# Adaptadora_AVR-Mega-U4_44pin.net
KiCad netlist of a schematic drawn in EAGLE
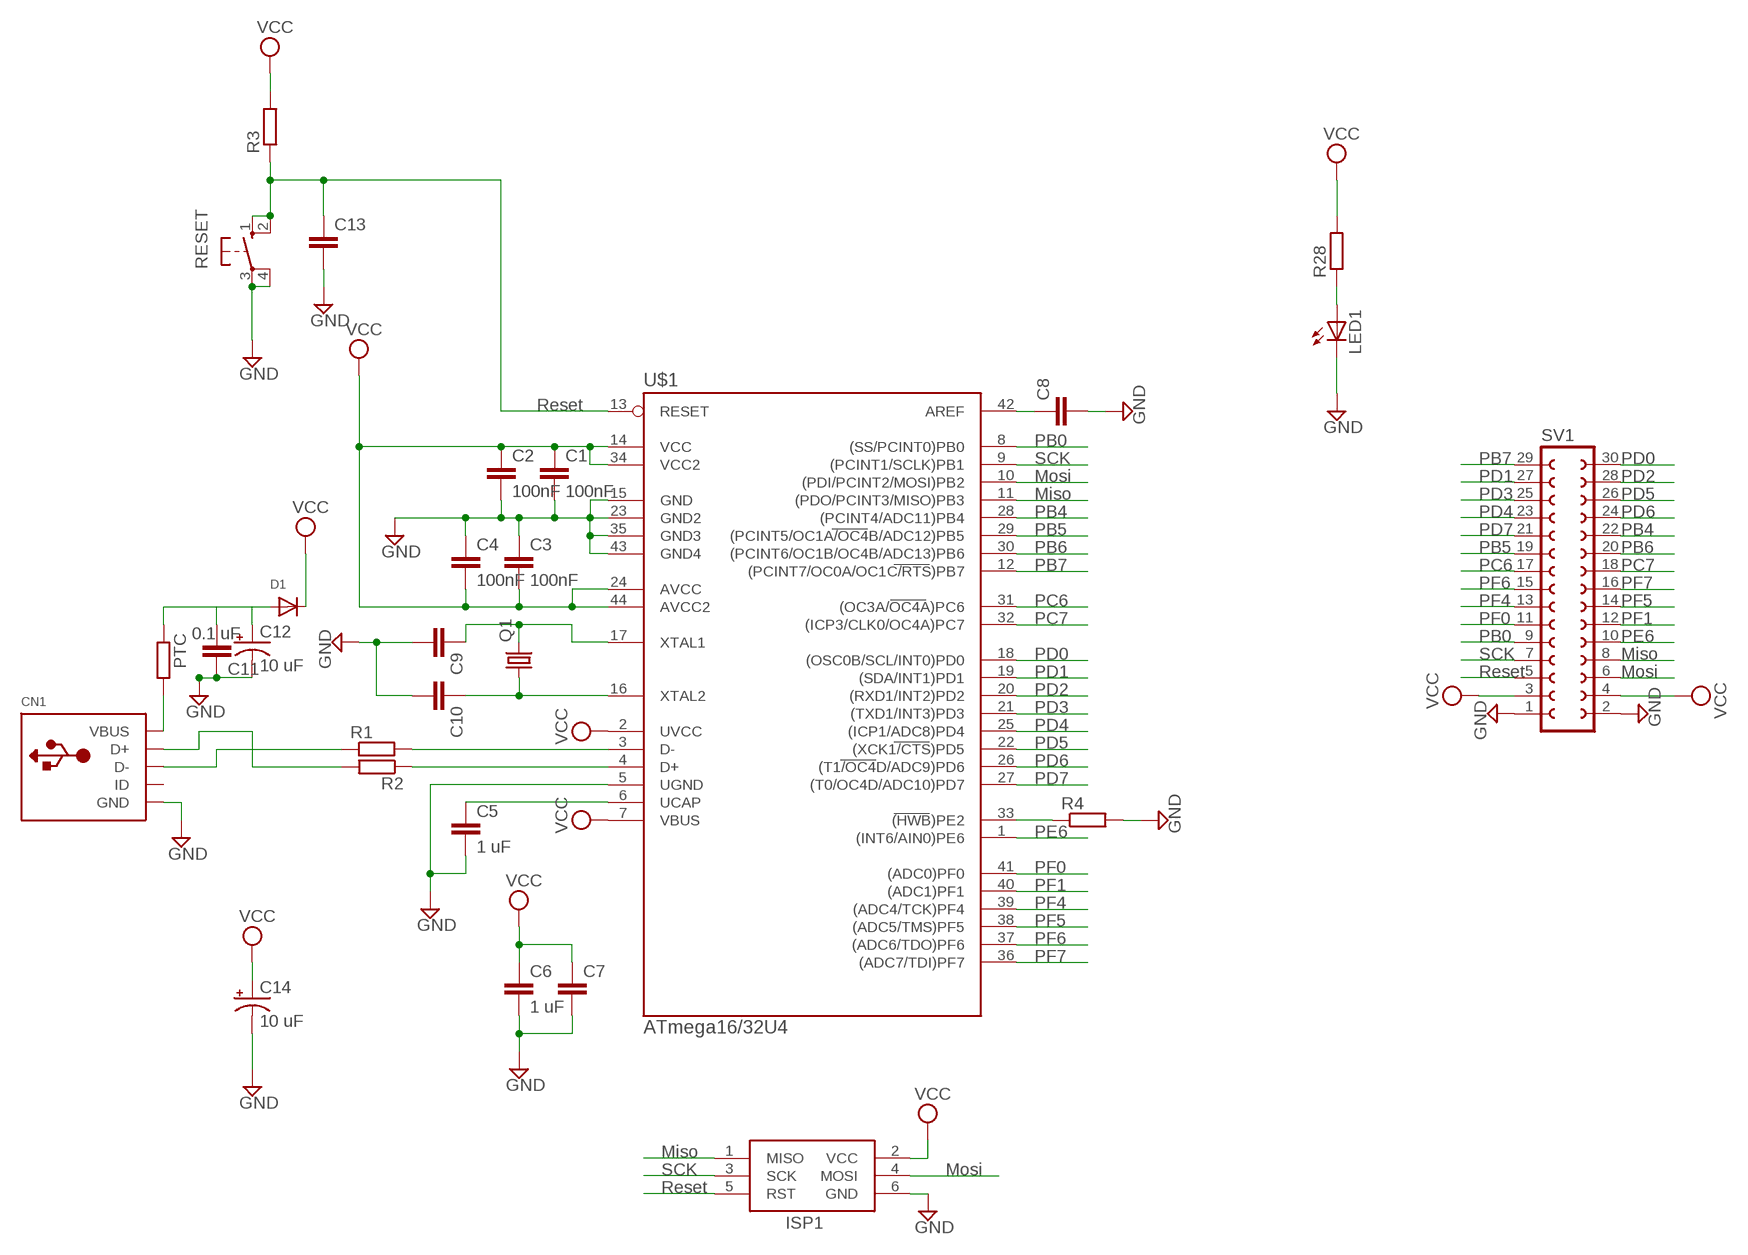
[diagram p0: schematic, sheet 1]

(export (version "E")
  (design (tool "Eeschema 10.0.6"))
  (components
    (comp (ref "C1")
      (value "100nF")
      (footprint "eagle-import:C1206")
      (libsource (lib "eagle-import") (part "C-EUC1206"))
    )
    (comp (ref "C2")
      (value "100nF")
      (footprint "eagle-import:C1206")
      (libsource (lib "eagle-import") (part "C-EUC1206"))
    )
    (comp (ref "C3")
      (value "100nF")
      (footprint "eagle-import:C1206")
      (libsource (lib "eagle-import") (part "C-EUC1206"))
    )
    (comp (ref "C4")
      (value "100nF")
      (footprint "eagle-import:C1206")
      (libsource (lib "eagle-import") (part "C-EUC1206"))
    )
    (comp (ref "C5")
      (value "1 uF")
      (footprint "eagle-import:C1206")
      (libsource (lib "eagle-import") (part "C-EUC1206"))
    )
    (comp (ref "C6")
      (value "1 uF")
      (footprint "eagle-import:C1206")
      (libsource (lib "eagle-import") (part "C-EUC1206"))
    )
    (comp (ref "C7")
      (value "C-EUC1206")
      (footprint "eagle-import:C1206")
      (libsource (lib "eagle-import") (part "C-EUC1206"))
    )
    (comp (ref "C8")
      (value "C-EUC1206")
      (footprint "eagle-import:C1206")
      (libsource (lib "eagle-import") (part "C-EUC1206"))
    )
    (comp (ref "C9")
      (value "C-EUC1206")
      (footprint "eagle-import:C1206")
      (libsource (lib "eagle-import") (part "C-EUC1206"))
    )
    (comp (ref "C10")
      (value "C-EUC1206")
      (footprint "eagle-import:C1206")
      (libsource (lib "eagle-import") (part "C-EUC1206"))
    )
    (comp (ref "C11")
      (value "0.1 uF")
      (footprint "eagle-import:C1206")
      (libsource (lib "eagle-import") (part "C-EUC1206"))
    )
    (comp (ref "C12")
      (value "10 uF")
      (footprint "eagle-import:EIA3216")
      (libsource (lib "eagle-import") (part "CAP_POL1206"))
    )
    (comp (ref "C13")
      (value "C-EUC1206")
      (footprint "eagle-import:C1206")
      (libsource (lib "eagle-import") (part "C-EUC1206"))
    )
    (comp (ref "C14")
      (value "10 uF")
      (footprint "eagle-import:EIA3216")
      (libsource (lib "eagle-import") (part "CAP_POL1206"))
    )
    (comp (ref "CN1")
      (value "USBMINIB")
      (footprint "eagle-import:USB-MINIB")
      (libsource (lib "eagle-import") (part "USBMINIB"))
    )
    (comp (ref "D1")
      (value "DIODESOD-123")
      (footprint "eagle-import:SOD-123")
      (libsource (lib "eagle-import") (part "DIODESOD-123"))
    )
    (comp (ref "ISP1")
      (value "AVRISP-6")
      (footprint "eagle-import:AVRISP")
      (libsource (lib "eagle-import") (part "AVRISP-6"))
    )
    (comp (ref "LED1")
      (value "LEDCHIPLED_1206")
      (footprint "eagle-import:CHIPLED_1206")
      (libsource (lib "eagle-import") (part "LEDCHIPLED_1206"))
    )
    (comp (ref "PTC")
      (value "R-EU_R1206")
      (footprint "eagle-import:R1206")
      (libsource (lib "eagle-import") (part "R-EU_R1206"))
    )
    (comp (ref "Q1")
      (value "CRYSTALHC49UP")
      (footprint "eagle-import:HC49UP")
      (fields (field (name "OC_FARNELL") "unknown") (field (name "OC_NEWARK") "unknown"))
      (libsource (lib "eagle-import") (part "CRYSTALHC49UP"))
    )
    (comp (ref "R1")
      (value "R-EU_R1206")
      (footprint "eagle-import:R1206")
      (libsource (lib "eagle-import") (part "R-EU_R1206"))
    )
    (comp (ref "R2")
      (value "R-EU_R1206")
      (footprint "eagle-import:R1206")
      (libsource (lib "eagle-import") (part "R-EU_R1206"))
    )
    (comp (ref "R3")
      (value "R-EU_R1206")
      (footprint "eagle-import:R1206")
      (libsource (lib "eagle-import") (part "R-EU_R1206"))
    )
    (comp (ref "R4")
      (value "R-EU_R1206")
      (footprint "eagle-import:R1206")
      (libsource (lib "eagle-import") (part "R-EU_R1206"))
    )
    (comp (ref "R28")
      (value "R-EU_R1206")
      (footprint "eagle-import:R1206")
      (libsource (lib "eagle-import") (part "R-EU_R1206"))
    )
    (comp (ref "RESET")
      (value "10-XX")
      (footprint "eagle-import:B3F-10XX")
      (fields (field (name "MPN") "B3F-1000"))
      (libsource (lib "eagle-import") (part "10-XX"))
    )
    (comp (ref "SV1")
      (value "FE15-2")
      (footprint "eagle-import:FE15-2")
      (libsource (lib "eagle-import") (part "FE15-2"))
    )
    (comp (ref "U$1")
      (value "ATmega16/32U4")
      (footprint "eagle-import:TQFP44")
      (libsource (lib "eagle-import") (part "ATMEGA32U4-AU"))
    )
  )
  (nets
    (net (code "1") (name "/MISO") (class "Default")
      (node (ref "ISP1") (pin "1") (pinfunction "MISO_1") (pintype "input"))
      (node (ref "SV1") (pin "8") (pinfunction "8_8") (pintype "passive"))
      (node (ref "U$1") (pin "11") (pinfunction "(PDO/PCINT3/MISO)PB3_11") (pintype "bidirectional"))
    )
    (net (code "2") (name "/MOSI") (class "Default")
      (node (ref "ISP1") (pin "4") (pinfunction "MOSI_4") (pintype "output"))
      (node (ref "SV1") (pin "6") (pinfunction "6_6") (pintype "passive"))
      (node (ref "U$1") (pin "10") (pinfunction "(PDI/PCINT2/MOSI)PB2_10") (pintype "bidirectional"))
    )
    (net (code "3") (name "/PB0") (class "Default")
      (node (ref "SV1") (pin "9") (pinfunction "9_9") (pintype "passive"))
      (node (ref "U$1") (pin "8") (pinfunction "(SS/PCINT0)PB0_8") (pintype "bidirectional"))
    )
    (net (code "4") (name "/PB4") (class "Default")
      (node (ref "SV1") (pin "22") (pinfunction "22_22") (pintype "passive"))
      (node (ref "U$1") (pin "28") (pinfunction "(PCINT4/ADC11)PB4_28") (pintype "bidirectional"))
    )
    (net (code "5") (name "/PB5") (class "Default")
      (node (ref "SV1") (pin "19") (pinfunction "19_19") (pintype "passive"))
      (node (ref "U$1") (pin "29") (pinfunction "(PCINT5/OC1A/OC4B/ADC12)PB5_29") (pintype "bidirectional"))
    )
    (net (code "6") (name "/PB6") (class "Default")
      (node (ref "SV1") (pin "20") (pinfunction "20_20") (pintype "passive"))
      (node (ref "U$1") (pin "30") (pinfunction "(PCINT6/OC1B/OC4B/ADC13)PB6_30") (pintype "bidirectional"))
    )
    (net (code "7") (name "/PB7") (class "Default")
      (node (ref "SV1") (pin "29") (pinfunction "29_29") (pintype "passive"))
      (node (ref "U$1") (pin "12") (pinfunction "(PCINT7/OC0A/OC1C/RTS)PB7_12") (pintype "bidirectional"))
    )
    (net (code "8") (name "/PC6") (class "Default")
      (node (ref "SV1") (pin "17") (pinfunction "17_17") (pintype "passive"))
      (node (ref "U$1") (pin "31") (pinfunction "(OC3A/OC4A)PC6_31") (pintype "bidirectional"))
    )
    (net (code "9") (name "/PC7") (class "Default")
      (node (ref "SV1") (pin "18") (pinfunction "18_18") (pintype "passive"))
      (node (ref "U$1") (pin "32") (pinfunction "(ICP3/CLK0/OC4A)PC7_32") (pintype "bidirectional"))
    )
    (net (code "10") (name "/PD0") (class "Default")
      (node (ref "SV1") (pin "30") (pinfunction "30_30") (pintype "passive"))
      (node (ref "U$1") (pin "18") (pinfunction "(OSC0B/SCL/INT0)PD0_18") (pintype "bidirectional"))
    )
    (net (code "11") (name "/PD1") (class "Default")
      (node (ref "SV1") (pin "27") (pinfunction "27_27") (pintype "passive"))
      (node (ref "U$1") (pin "19") (pinfunction "(SDA/INT1)PD1_19") (pintype "bidirectional"))
    )
    (net (code "12") (name "/PD2") (class "Default")
      (node (ref "SV1") (pin "28") (pinfunction "28_28") (pintype "passive"))
      (node (ref "U$1") (pin "20") (pinfunction "(RXD1/INT2)PD2_20") (pintype "bidirectional"))
    )
    (net (code "13") (name "/PD3") (class "Default")
      (node (ref "SV1") (pin "25") (pinfunction "25_25") (pintype "passive"))
      (node (ref "U$1") (pin "21") (pinfunction "(TXD1/INT3)PD3_21") (pintype "bidirectional"))
    )
    (net (code "14") (name "/PD4") (class "Default")
      (node (ref "SV1") (pin "23") (pinfunction "23_23") (pintype "passive"))
      (node (ref "U$1") (pin "25") (pinfunction "(ICP1/ADC8)PD4_25") (pintype "bidirectional"))
    )
    (net (code "15") (name "/PD5") (class "Default")
      (node (ref "SV1") (pin "26") (pinfunction "26_26") (pintype "passive"))
      (node (ref "U$1") (pin "22") (pinfunction "(XCK1/CTS)PD5_22") (pintype "bidirectional"))
    )
    (net (code "16") (name "/PD6") (class "Default")
      (node (ref "SV1") (pin "24") (pinfunction "24_24") (pintype "passive"))
      (node (ref "U$1") (pin "26") (pinfunction "(T1/OC4D/ADC9)PD6_26") (pintype "bidirectional"))
    )
    (net (code "17") (name "/PD7") (class "Default")
      (node (ref "SV1") (pin "21") (pinfunction "21_21") (pintype "passive"))
      (node (ref "U$1") (pin "27") (pinfunction "(T0/OC4D/ADC10)PD7_27") (pintype "bidirectional"))
    )
    (net (code "18") (name "/PE6") (class "Default")
      (node (ref "SV1") (pin "10") (pinfunction "10_10") (pintype "passive"))
      (node (ref "U$1") (pin "1") (pinfunction "(INT6/AIN0)PE6_1") (pintype "bidirectional"))
    )
    (net (code "19") (name "/PF0") (class "Default")
      (node (ref "SV1") (pin "11") (pinfunction "11_11") (pintype "passive"))
      (node (ref "U$1") (pin "41") (pinfunction "(ADC0)PF0_41") (pintype "bidirectional"))
    )
    (net (code "20") (name "/PF1") (class "Default")
      (node (ref "SV1") (pin "12") (pinfunction "12_12") (pintype "passive"))
      (node (ref "U$1") (pin "40") (pinfunction "(ADC1)PF1_40") (pintype "bidirectional"))
    )
    (net (code "21") (name "/PF4") (class "Default")
      (node (ref "SV1") (pin "13") (pinfunction "13_13") (pintype "passive"))
      (node (ref "U$1") (pin "39") (pinfunction "(ADC4/TCK)PF4_39") (pintype "bidirectional"))
    )
    (net (code "22") (name "/PF5") (class "Default")
      (node (ref "SV1") (pin "14") (pinfunction "14_14") (pintype "passive"))
      (node (ref "U$1") (pin "38") (pinfunction "(ADC5/TMS)PF5_38") (pintype "bidirectional"))
    )
    (net (code "23") (name "/PF6") (class "Default")
      (node (ref "SV1") (pin "15") (pinfunction "15_15") (pintype "passive"))
      (node (ref "U$1") (pin "37") (pinfunction "(ADC6/TDO)PF6_37") (pintype "bidirectional"))
    )
    (net (code "24") (name "/PF7") (class "Default")
      (node (ref "SV1") (pin "16") (pinfunction "16_16") (pintype "passive"))
      (node (ref "U$1") (pin "36") (pinfunction "(ADC7/TDI)PF7_36") (pintype "bidirectional"))
    )
    (net (code "25") (name "/RESET") (class "Default")
      (node (ref "C13") (pin "1") (pinfunction "1_1") (pintype "passive"))
      (node (ref "ISP1") (pin "5") (pinfunction "RST_5") (pintype "output"))
      (node (ref "R3") (pin "1") (pinfunction "1_1") (pintype "passive"))
      (node (ref "RESET") (pin "1") (pinfunction "S_1") (pintype "passive"))
      (node (ref "RESET") (pin "2") (pinfunction "S1_2") (pintype "passive"))
      (node (ref "SV1") (pin "5") (pinfunction "5_5") (pintype "passive"))
      (node (ref "U$1") (pin "13") (pinfunction "RESET_13") (pintype "bidirectional"))
    )
    (net (code "26") (name "/SCK") (class "Default")
      (node (ref "ISP1") (pin "3") (pinfunction "SCK_3") (pintype "output"))
      (node (ref "SV1") (pin "7") (pinfunction "7_7") (pintype "passive"))
      (node (ref "U$1") (pin "9") (pinfunction "(PCINT1/SCLK)PB1_9") (pintype "bidirectional"))
    )
    (net (code "27") (name "GND") (class "Default")
      (node (ref "C1") (pin "2") (pinfunction "2_2") (pintype "passive"))
      (node (ref "C10") (pin "2") (pinfunction "2_2") (pintype "passive"))
      (node (ref "C11") (pin "2") (pinfunction "2_2") (pintype "passive"))
      (node (ref "C12") (pin "C") (pinfunction "-_C") (pintype "passive"))
      (node (ref "C13") (pin "2") (pinfunction "2_2") (pintype "passive"))
      (node (ref "C14") (pin "C") (pinfunction "-_C") (pintype "passive"))
      (node (ref "C2") (pin "2") (pinfunction "2_2") (pintype "passive"))
      (node (ref "C3") (pin "1") (pinfunction "1_1") (pintype "passive"))
      (node (ref "C4") (pin "1") (pinfunction "1_1") (pintype "passive"))
      (node (ref "C5") (pin "2") (pinfunction "2_2") (pintype "passive"))
      (node (ref "C6") (pin "2") (pinfunction "2_2") (pintype "passive"))
      (node (ref "C7") (pin "2") (pinfunction "2_2") (pintype "passive"))
      (node (ref "C8") (pin "2") (pinfunction "2_2") (pintype "passive"))
      (node (ref "C9") (pin "2") (pinfunction "2_2") (pintype "passive"))
      (node (ref "CN1") (pin "GND") (pinfunction "GND_GND") (pintype "power_in"))
      (node (ref "ISP1") (pin "6") (pinfunction "GND_6") (pintype "power_in"))
      (node (ref "LED1") (pin "C") (pinfunction "C_C") (pintype "passive"))
      (node (ref "R4") (pin "2") (pinfunction "2_2") (pintype "passive"))
      (node (ref "RESET") (pin "3") (pinfunction "P_3") (pintype "passive"))
      (node (ref "RESET") (pin "4") (pinfunction "P1_4") (pintype "passive"))
      (node (ref "SV1") (pin "1") (pinfunction "1_1") (pintype "passive"))
      (node (ref "SV1") (pin "2") (pinfunction "2_2") (pintype "passive"))
      (node (ref "U$1") (pin "15") (pinfunction "GND_15") (pintype "bidirectional"))
      (node (ref "U$1") (pin "23") (pinfunction "GND2_23") (pintype "bidirectional"))
      (node (ref "U$1") (pin "35") (pinfunction "GND3_35") (pintype "bidirectional"))
      (node (ref "U$1") (pin "43") (pinfunction "GND4_43") (pintype "bidirectional"))
      (node (ref "U$1") (pin "5") (pinfunction "UGND_5") (pintype "bidirectional"))
    )
    (net (code "28") (name "Net-(C12-+)") (class "Default")
      (node (ref "C11") (pin "1") (pinfunction "1_1") (pintype "passive"))
      (node (ref "C12") (pin "A") (pinfunction "+_A") (pintype "passive"))
      (node (ref "D1") (pin "A") (pinfunction "A_A") (pintype "passive"))
      (node (ref "PTC") (pin "1") (pinfunction "1_1") (pintype "passive"))
    )
    (net (code "29") (name "Net-(CN1-PadD+)") (class "Default")
      (node (ref "CN1") (pin "D+") (pinfunction "D+_D+") (pintype "bidirectional"))
      (node (ref "R2") (pin "2") (pinfunction "2_2") (pintype "passive"))
    )
    (net (code "30") (name "Net-(CN1-PadD-)") (class "Default")
      (node (ref "CN1") (pin "D-") (pinfunction "D-_D-") (pintype "bidirectional"))
      (node (ref "R1") (pin "1") (pinfunction "1_1") (pintype "passive"))
    )
    (net (code "31") (name "Net-(CN1-PadVBUS)") (class "Default")
      (node (ref "CN1") (pin "VBUS") (pinfunction "VBUS_VBUS") (pintype "power_in"))
      (node (ref "PTC") (pin "2") (pinfunction "2_2") (pintype "passive"))
    )
    (net (code "32") (name "Net-(LED1-PadA)") (class "Default")
      (node (ref "LED1") (pin "A") (pinfunction "A_A") (pintype "passive"))
      (node (ref "R28") (pin "1") (pinfunction "1_1") (pintype "passive"))
    )
    (net (code "33") (name "Net-(U$1-(HWB)PE2)") (class "Default")
      (node (ref "R4") (pin "1") (pinfunction "1_1") (pintype "passive"))
      (node (ref "U$1") (pin "33") (pinfunction "(HWB)PE2_33") (pintype "bidirectional"))
    )
    (net (code "34") (name "Net-(U$1-AREF)") (class "Default")
      (node (ref "C8") (pin "1") (pinfunction "1_1") (pintype "passive"))
      (node (ref "U$1") (pin "42") (pinfunction "AREF_42") (pintype "bidirectional"))
    )
    (net (code "35") (name "Net-(U$1-D+)") (class "Default")
      (node (ref "R2") (pin "1") (pinfunction "1_1") (pintype "passive"))
      (node (ref "U$1") (pin "4") (pinfunction "D+_4") (pintype "bidirectional"))
    )
    (net (code "36") (name "Net-(U$1-D-)") (class "Default")
      (node (ref "R1") (pin "2") (pinfunction "2_2") (pintype "passive"))
      (node (ref "U$1") (pin "3") (pinfunction "D-_3") (pintype "bidirectional"))
    )
    (net (code "37") (name "Net-(U$1-UCAP)") (class "Default")
      (node (ref "C5") (pin "1") (pinfunction "1_1") (pintype "passive"))
      (node (ref "U$1") (pin "6") (pinfunction "UCAP_6") (pintype "bidirectional"))
    )
    (net (code "38") (name "Net-(U$1-XTAL1)") (class "Default")
      (node (ref "C9") (pin "1") (pinfunction "1_1") (pintype "passive"))
      (node (ref "Q1") (pin "2") (pinfunction "2_2") (pintype "passive"))
      (node (ref "U$1") (pin "17") (pinfunction "XTAL1_17") (pintype "bidirectional"))
    )
    (net (code "39") (name "Net-(U$1-XTAL2)") (class "Default")
      (node (ref "C10") (pin "1") (pinfunction "1_1") (pintype "passive"))
      (node (ref "Q1") (pin "1") (pinfunction "1_1") (pintype "passive"))
      (node (ref "U$1") (pin "16") (pinfunction "XTAL2_16") (pintype "bidirectional"))
    )
    (net (code "40") (name "VCC") (class "Default")
      (node (ref "C1") (pin "1") (pinfunction "1_1") (pintype "passive"))
      (node (ref "C14") (pin "A") (pinfunction "+_A") (pintype "passive"))
      (node (ref "C2") (pin "1") (pinfunction "1_1") (pintype "passive"))
      (node (ref "C3") (pin "2") (pinfunction "2_2") (pintype "passive"))
      (node (ref "C4") (pin "2") (pinfunction "2_2") (pintype "passive"))
      (node (ref "C6") (pin "1") (pinfunction "1_1") (pintype "passive"))
      (node (ref "C7") (pin "1") (pinfunction "1_1") (pintype "passive"))
      (node (ref "D1") (pin "C") (pinfunction "C_C") (pintype "passive"))
      (node (ref "ISP1") (pin "2") (pinfunction "VCC_2") (pintype "power_in"))
      (node (ref "R28") (pin "2") (pinfunction "2_2") (pintype "passive"))
      (node (ref "R3") (pin "2") (pinfunction "2_2") (pintype "passive"))
      (node (ref "SV1") (pin "3") (pinfunction "3_3") (pintype "passive"))
      (node (ref "SV1") (pin "4") (pinfunction "4_4") (pintype "passive"))
      (node (ref "U$1") (pin "14") (pinfunction "VCC_14") (pintype "bidirectional"))
      (node (ref "U$1") (pin "2") (pinfunction "UVCC_2") (pintype "bidirectional"))
      (node (ref "U$1") (pin "24") (pinfunction "AVCC_24") (pintype "bidirectional"))
      (node (ref "U$1") (pin "34") (pinfunction "VCC2_34") (pintype "bidirectional"))
      (node (ref "U$1") (pin "44") (pinfunction "AVCC2_44") (pintype "bidirectional"))
      (node (ref "U$1") (pin "7") (pinfunction "VBUS_7") (pintype "bidirectional"))
    )
    (net (code "41") (name "unconnected-(CN1-PadID)") (class "Default")
      (node (ref "CN1") (pin "ID") (pinfunction "ID_ID") (pintype "bidirectional"))
    )
  )
)
